# atem_tally_receiver.net
KiCad netlist of a schematic drawn in EAGLE
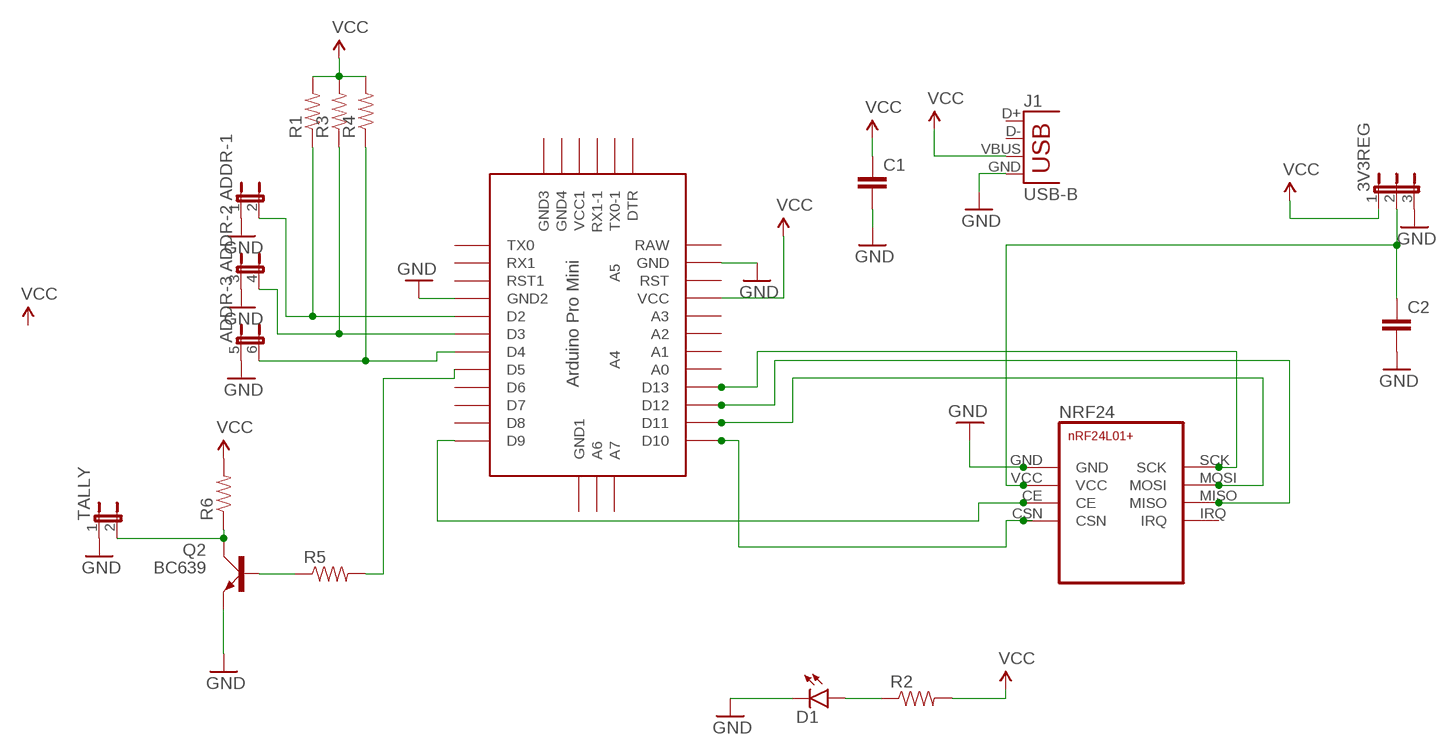
[diagram p0: schematic, sheet 1]

(export (version "E")
  (design (tool "Eeschema 10.0.6"))
  (components
    (comp (ref "3V3REG")
      (value "JP2E")
      (footprint "eagle-import:JP2")
      (libsource (lib "eagle-import") (part "JP2E"))
    )
    (comp (ref "ADDR")
      (value "JP3QE")
      (footprint "eagle-import:JP3Q")
      (libsource (lib "eagle-import") (part "JP3QE"))
    )
    (comp (ref "C1")
      (value "C-EU025-050X050")
      (footprint "eagle-import:C025-050X050")
      (libsource (lib "eagle-import") (part "C-EU025-050X050"))
    )
    (comp (ref "C2")
      (value "C-EU025-050X050")
      (footprint "eagle-import:C025-050X050")
      (libsource (lib "eagle-import") (part "C-EU025-050X050"))
    )
    (comp (ref "D1")
      (value "LED3MM")
      (footprint "eagle-import:LED3MM")
      (libsource (lib "eagle-import") (part "LED3MM"))
    )
    (comp (ref "J1")
      (value "USB-B")
      (footprint "eagle-import:USB-B-PTH")
      (libsource (lib "eagle-import") (part "USBPTH"))
    )
    (comp (ref "NRF24")
      (value "NRF24L01+")
      (footprint "eagle-import:NRF24L01+")
      (libsource (lib "eagle-import") (part "NRF24L01+"))
    )
    (comp (ref "Q2")
      (value "BC639")
      (footprint "eagle-import:SOT54D")
      (libsource (lib "eagle-import") (part "BC639"))
    )
    (comp (ref "R1")
      (value "RESISTORAXIAL-0.3")
      (footprint "eagle-import:AXIAL-0.3")
      (libsource (lib "eagle-import") (part "RESISTORAXIAL-0.3"))
    )
    (comp (ref "R2")
      (value "RESISTORAXIAL-0.3")
      (footprint "eagle-import:AXIAL-0.3")
      (libsource (lib "eagle-import") (part "RESISTORAXIAL-0.3"))
    )
    (comp (ref "R3")
      (value "RESISTORAXIAL-0.3")
      (footprint "eagle-import:AXIAL-0.3")
      (libsource (lib "eagle-import") (part "RESISTORAXIAL-0.3"))
    )
    (comp (ref "R4")
      (value "RESISTORAXIAL-0.3")
      (footprint "eagle-import:AXIAL-0.3")
      (libsource (lib "eagle-import") (part "RESISTORAXIAL-0.3"))
    )
    (comp (ref "R5")
      (value "RESISTORAXIAL-0.3")
      (footprint "eagle-import:AXIAL-0.3")
      (libsource (lib "eagle-import") (part "RESISTORAXIAL-0.3"))
    )
    (comp (ref "R6")
      (value "RESISTORPTH-1W")
      (footprint "eagle-import:AXIAL-0.6")
      (libsource (lib "eagle-import") (part "SparkFun-Passives_RESISTORPTH-1W"))
    )
    (comp (ref "TALLY")
      (value "JP1E")
      (footprint "eagle-import:JP1")
      (libsource (lib "eagle-import") (part "JP1E"))
    )
    (comp (ref "U$1")
      (value "ABK-PRO-MINI")
      (footprint "eagle-import:ABK-PRO-MINI")
      (libsource (lib "eagle-import") (part "ABK-PRO-MINI"))
    )
  )
  (nets
    (net (code "1") (name "GND") (class "Default")
      (node (ref "3V3REG") (pin "3") (pinfunction "3_3") (pintype "passive"))
      (node (ref "ADDR") (pin "1") (pinfunction "1_1") (pintype "passive"))
      (node (ref "ADDR") (pin "3") (pinfunction "1_3") (pintype "passive"))
      (node (ref "ADDR") (pin "5") (pinfunction "1_5") (pintype "passive"))
      (node (ref "C1") (pin "2") (pinfunction "2_2") (pintype "passive"))
      (node (ref "C2") (pin "2") (pinfunction "2_2") (pintype "passive"))
      (node (ref "D1") (pin "K") (pinfunction "C_K") (pintype "passive"))
      (node (ref "J1") (pin "GND") (pinfunction "GND_GND") (pintype "bidirectional"))
      (node (ref "NRF24") (pin "GND") (pinfunction "GND_GND") (pintype "power_in"))
      (node (ref "Q2") (pin "E") (pinfunction "E_E") (pintype "passive"))
      (node (ref "TALLY") (pin "1") (pinfunction "1_1") (pintype "passive"))
      (node (ref "U$1") (pin "GND") (pinfunction "GND_GND") (pintype "bidirectional"))
      (node (ref "U$1") (pin "GND1") (pinfunction "GND2_GND1") (pintype "bidirectional"))
    )
    (net (code "2") (name "Net-(3V3REG-Pad2)") (class "Default")
      (node (ref "3V3REG") (pin "2") (pinfunction "2_2") (pintype "passive"))
      (node (ref "C2") (pin "1") (pinfunction "1_1") (pintype "passive"))
      (node (ref "NRF24") (pin "VCC") (pinfunction "VCC_VCC") (pintype "power_in"))
    )
    (net (code "3") (name "Net-(ADDRB-2)") (class "Default")
      (node (ref "ADDR") (pin "4") (pinfunction "2_4") (pintype "passive"))
      (node (ref "R3") (pin "P$1") (pinfunction "1_P$1") (pintype "passive"))
      (node (ref "U$1") (pin "D3") (pinfunction "D3_D3") (pintype "bidirectional"))
    )
    (net (code "4") (name "Net-(ADDRC-2)") (class "Default")
      (node (ref "ADDR") (pin "6") (pinfunction "2_6") (pintype "passive"))
      (node (ref "R4") (pin "P$1") (pinfunction "1_P$1") (pintype "passive"))
      (node (ref "U$1") (pin "D4") (pinfunction "D4_D4") (pintype "bidirectional"))
    )
    (net (code "5") (name "Net-(NRF24-PadCE)") (class "Default")
      (node (ref "NRF24") (pin "CE") (pinfunction "CE_CE") (pintype "bidirectional"))
      (node (ref "U$1") (pin "D9") (pinfunction "D9_D9") (pintype "bidirectional"))
    )
    (net (code "6") (name "Net-(NRF24-PadCSN)") (class "Default")
      (node (ref "NRF24") (pin "CSN") (pinfunction "CSN_CSN") (pintype "bidirectional"))
      (node (ref "U$1") (pin "D10") (pinfunction "D10_D10") (pintype "bidirectional"))
    )
    (net (code "7") (name "Net-(NRF24-PadMISO)") (class "Default")
      (node (ref "NRF24") (pin "MISO") (pinfunction "MISO_MISO") (pintype "bidirectional"))
      (node (ref "U$1") (pin "D12") (pinfunction "D12_D12") (pintype "bidirectional"))
    )
    (net (code "8") (name "Net-(NRF24-PadMOSI)") (class "Default")
      (node (ref "NRF24") (pin "MOSI") (pinfunction "MOSI_MOSI") (pintype "bidirectional"))
      (node (ref "U$1") (pin "D11") (pinfunction "D11_D11") (pintype "bidirectional"))
    )
    (net (code "9") (name "Net-(NRF24-PadSCK)") (class "Default")
      (node (ref "NRF24") (pin "SCK") (pinfunction "SCK_SCK") (pintype "bidirectional"))
      (node (ref "U$1") (pin "D13") (pinfunction "D13_D13") (pintype "bidirectional"))
    )
    (net (code "10") (name "Net-(R1-1)") (class "Default")
      (node (ref "ADDR") (pin "2") (pinfunction "2_2") (pintype "passive"))
      (node (ref "R1") (pin "P$1") (pinfunction "1_P$1") (pintype "passive"))
      (node (ref "U$1") (pin "D2") (pinfunction "D2_D2") (pintype "bidirectional"))
    )
    (net (code "11") (name "Net-(R2-1)") (class "Default")
      (node (ref "D1") (pin "A") (pinfunction "A_A") (pintype "passive"))
      (node (ref "R2") (pin "P$1") (pinfunction "1_P$1") (pintype "passive"))
    )
    (net (code "12") (name "Net-(R5-1)") (class "Default")
      (node (ref "Q2") (pin "B") (pinfunction "B_B") (pintype "passive"))
      (node (ref "R5") (pin "P$1") (pinfunction "1_P$1") (pintype "passive"))
    )
    (net (code "13") (name "Net-(R5-2)") (class "Default")
      (node (ref "R5") (pin "P$2") (pinfunction "2_P$2") (pintype "passive"))
      (node (ref "U$1") (pin "D5") (pinfunction "D5_D5") (pintype "bidirectional"))
    )
    (net (code "14") (name "Net-(R6-1)") (class "Default")
      (node (ref "Q2") (pin "C") (pinfunction "C_C") (pintype "passive"))
      (node (ref "R6") (pin "P$1") (pinfunction "1_P$1") (pintype "passive"))
      (node (ref "TALLY") (pin "2") (pinfunction "2_2") (pintype "passive"))
    )
    (net (code "15") (name "VCC") (class "Default")
      (node (ref "3V3REG") (pin "1") (pinfunction "1_1") (pintype "passive"))
      (node (ref "C1") (pin "1") (pinfunction "1_1") (pintype "passive"))
      (node (ref "J1") (pin "VBUS") (pinfunction "VBUS_VBUS") (pintype "bidirectional"))
      (node (ref "R1") (pin "P$2") (pinfunction "2_P$2") (pintype "passive"))
      (node (ref "R2") (pin "P$2") (pinfunction "2_P$2") (pintype "passive"))
      (node (ref "R3") (pin "P$2") (pinfunction "2_P$2") (pintype "passive"))
      (node (ref "R4") (pin "P$2") (pinfunction "2_P$2") (pintype "passive"))
      (node (ref "R6") (pin "P$2") (pinfunction "2_P$2") (pintype "passive"))
      (node (ref "U$1") (pin "VCC") (pinfunction "VCC_VCC") (pintype "bidirectional"))
    )
    (net (code "16") (name "unconnected-(J1-PadD+)") (class "Default")
      (node (ref "J1") (pin "D+") (pinfunction "D+_D+") (pintype "bidirectional"))
    )
    (net (code "17") (name "unconnected-(J1-PadD-)") (class "Default")
      (node (ref "J1") (pin "D-") (pinfunction "D-_D-") (pintype "bidirectional"))
    )
    (net (code "18") (name "unconnected-(NRF24-PadIRQ)") (class "Default")
      (node (ref "NRF24") (pin "IRQ") (pinfunction "IRQ_IRQ") (pintype "bidirectional"))
    )
    (net (code "19") (name "unconnected-(U$1-GND1-PadGND4)") (class "Default")
      (node (ref "U$1") (pin "GND4") (pinfunction "GND1_GND4") (pintype "bidirectional"))
    )
    (net (code "20") (name "unconnected-(U$1-GND3-PadGND2)") (class "Default")
      (node (ref "U$1") (pin "GND2") (pinfunction "GND3_GND2") (pintype "bidirectional"))
    )
    (net (code "21") (name "unconnected-(U$1-GND4-PadGND3)") (class "Default")
      (node (ref "U$1") (pin "GND3") (pinfunction "GND4_GND3") (pintype "bidirectional"))
    )
    (net (code "22") (name "unconnected-(U$1-PadA0)") (class "Default")
      (node (ref "U$1") (pin "A0") (pinfunction "A0_A0") (pintype "bidirectional"))
    )
    (net (code "23") (name "unconnected-(U$1-PadA1)") (class "Default")
      (node (ref "U$1") (pin "A1") (pinfunction "A1_A1") (pintype "bidirectional"))
    )
    (net (code "24") (name "unconnected-(U$1-PadA2)") (class "Default")
      (node (ref "U$1") (pin "A2") (pinfunction "A2_A2") (pintype "bidirectional"))
    )
    (net (code "25") (name "unconnected-(U$1-PadA3)") (class "Default")
      (node (ref "U$1") (pin "A3") (pinfunction "A3_A3") (pintype "bidirectional"))
    )
    (net (code "26") (name "unconnected-(U$1-PadA4)") (class "Default")
      (node (ref "U$1") (pin "A4") (pinfunction "A4_A4") (pintype "bidirectional"))
    )
    (net (code "27") (name "unconnected-(U$1-PadA5)") (class "Default")
      (node (ref "U$1") (pin "A5") (pinfunction "A5_A5") (pintype "bidirectional"))
    )
    (net (code "28") (name "unconnected-(U$1-PadA6)") (class "Default")
      (node (ref "U$1") (pin "A6") (pinfunction "A6_A6") (pintype "bidirectional"))
    )
    (net (code "29") (name "unconnected-(U$1-PadA7)") (class "Default")
      (node (ref "U$1") (pin "A7") (pinfunction "A7_A7") (pintype "bidirectional"))
    )
    (net (code "30") (name "unconnected-(U$1-PadD6)") (class "Default")
      (node (ref "U$1") (pin "D6") (pinfunction "D6_D6") (pintype "bidirectional"))
    )
    (net (code "31") (name "unconnected-(U$1-PadD7)") (class "Default")
      (node (ref "U$1") (pin "D7") (pinfunction "D7_D7") (pintype "bidirectional"))
    )
    (net (code "32") (name "unconnected-(U$1-PadD8)") (class "Default")
      (node (ref "U$1") (pin "D8") (pinfunction "D8_D8") (pintype "bidirectional"))
    )
    (net (code "33") (name "unconnected-(U$1-PadDTR)") (class "Default")
      (node (ref "U$1") (pin "DTR") (pinfunction "DTR_DTR") (pintype "bidirectional"))
    )
    (net (code "34") (name "unconnected-(U$1-PadRAW)") (class "Default")
      (node (ref "U$1") (pin "RAW") (pinfunction "RAW_RAW") (pintype "bidirectional"))
    )
    (net (code "35") (name "unconnected-(U$1-PadRST)") (class "Default")
      (node (ref "U$1") (pin "RST") (pinfunction "RST_RST") (pintype "bidirectional"))
    )
    (net (code "36") (name "unconnected-(U$1-PadRST1)") (class "Default")
      (node (ref "U$1") (pin "RST1") (pinfunction "RST1_RST1") (pintype "bidirectional"))
    )
    (net (code "37") (name "unconnected-(U$1-PadRX1)") (class "Default")
      (node (ref "U$1") (pin "RX1") (pinfunction "RX1_RX1") (pintype "bidirectional"))
    )
    (net (code "38") (name "unconnected-(U$1-PadRX1-1)") (class "Default")
      (node (ref "U$1") (pin "RX1-1") (pinfunction "RX1-1_RX1-1") (pintype "bidirectional"))
    )
    (net (code "39") (name "unconnected-(U$1-PadTX0)") (class "Default")
      (node (ref "U$1") (pin "TX0") (pinfunction "TX0_TX0") (pintype "bidirectional"))
    )
    (net (code "40") (name "unconnected-(U$1-PadTX0-1)") (class "Default")
      (node (ref "U$1") (pin "TX0-1") (pinfunction "TX0-1_TX0-1") (pintype "bidirectional"))
    )
    (net (code "41") (name "unconnected-(U$1-PadVCC1)") (class "Default")
      (node (ref "U$1") (pin "VCC1") (pinfunction "VCC1_VCC1") (pintype "bidirectional"))
    )
  )
)
